# Demo.net
KiCad netlist of a schematic drawn in EAGLE
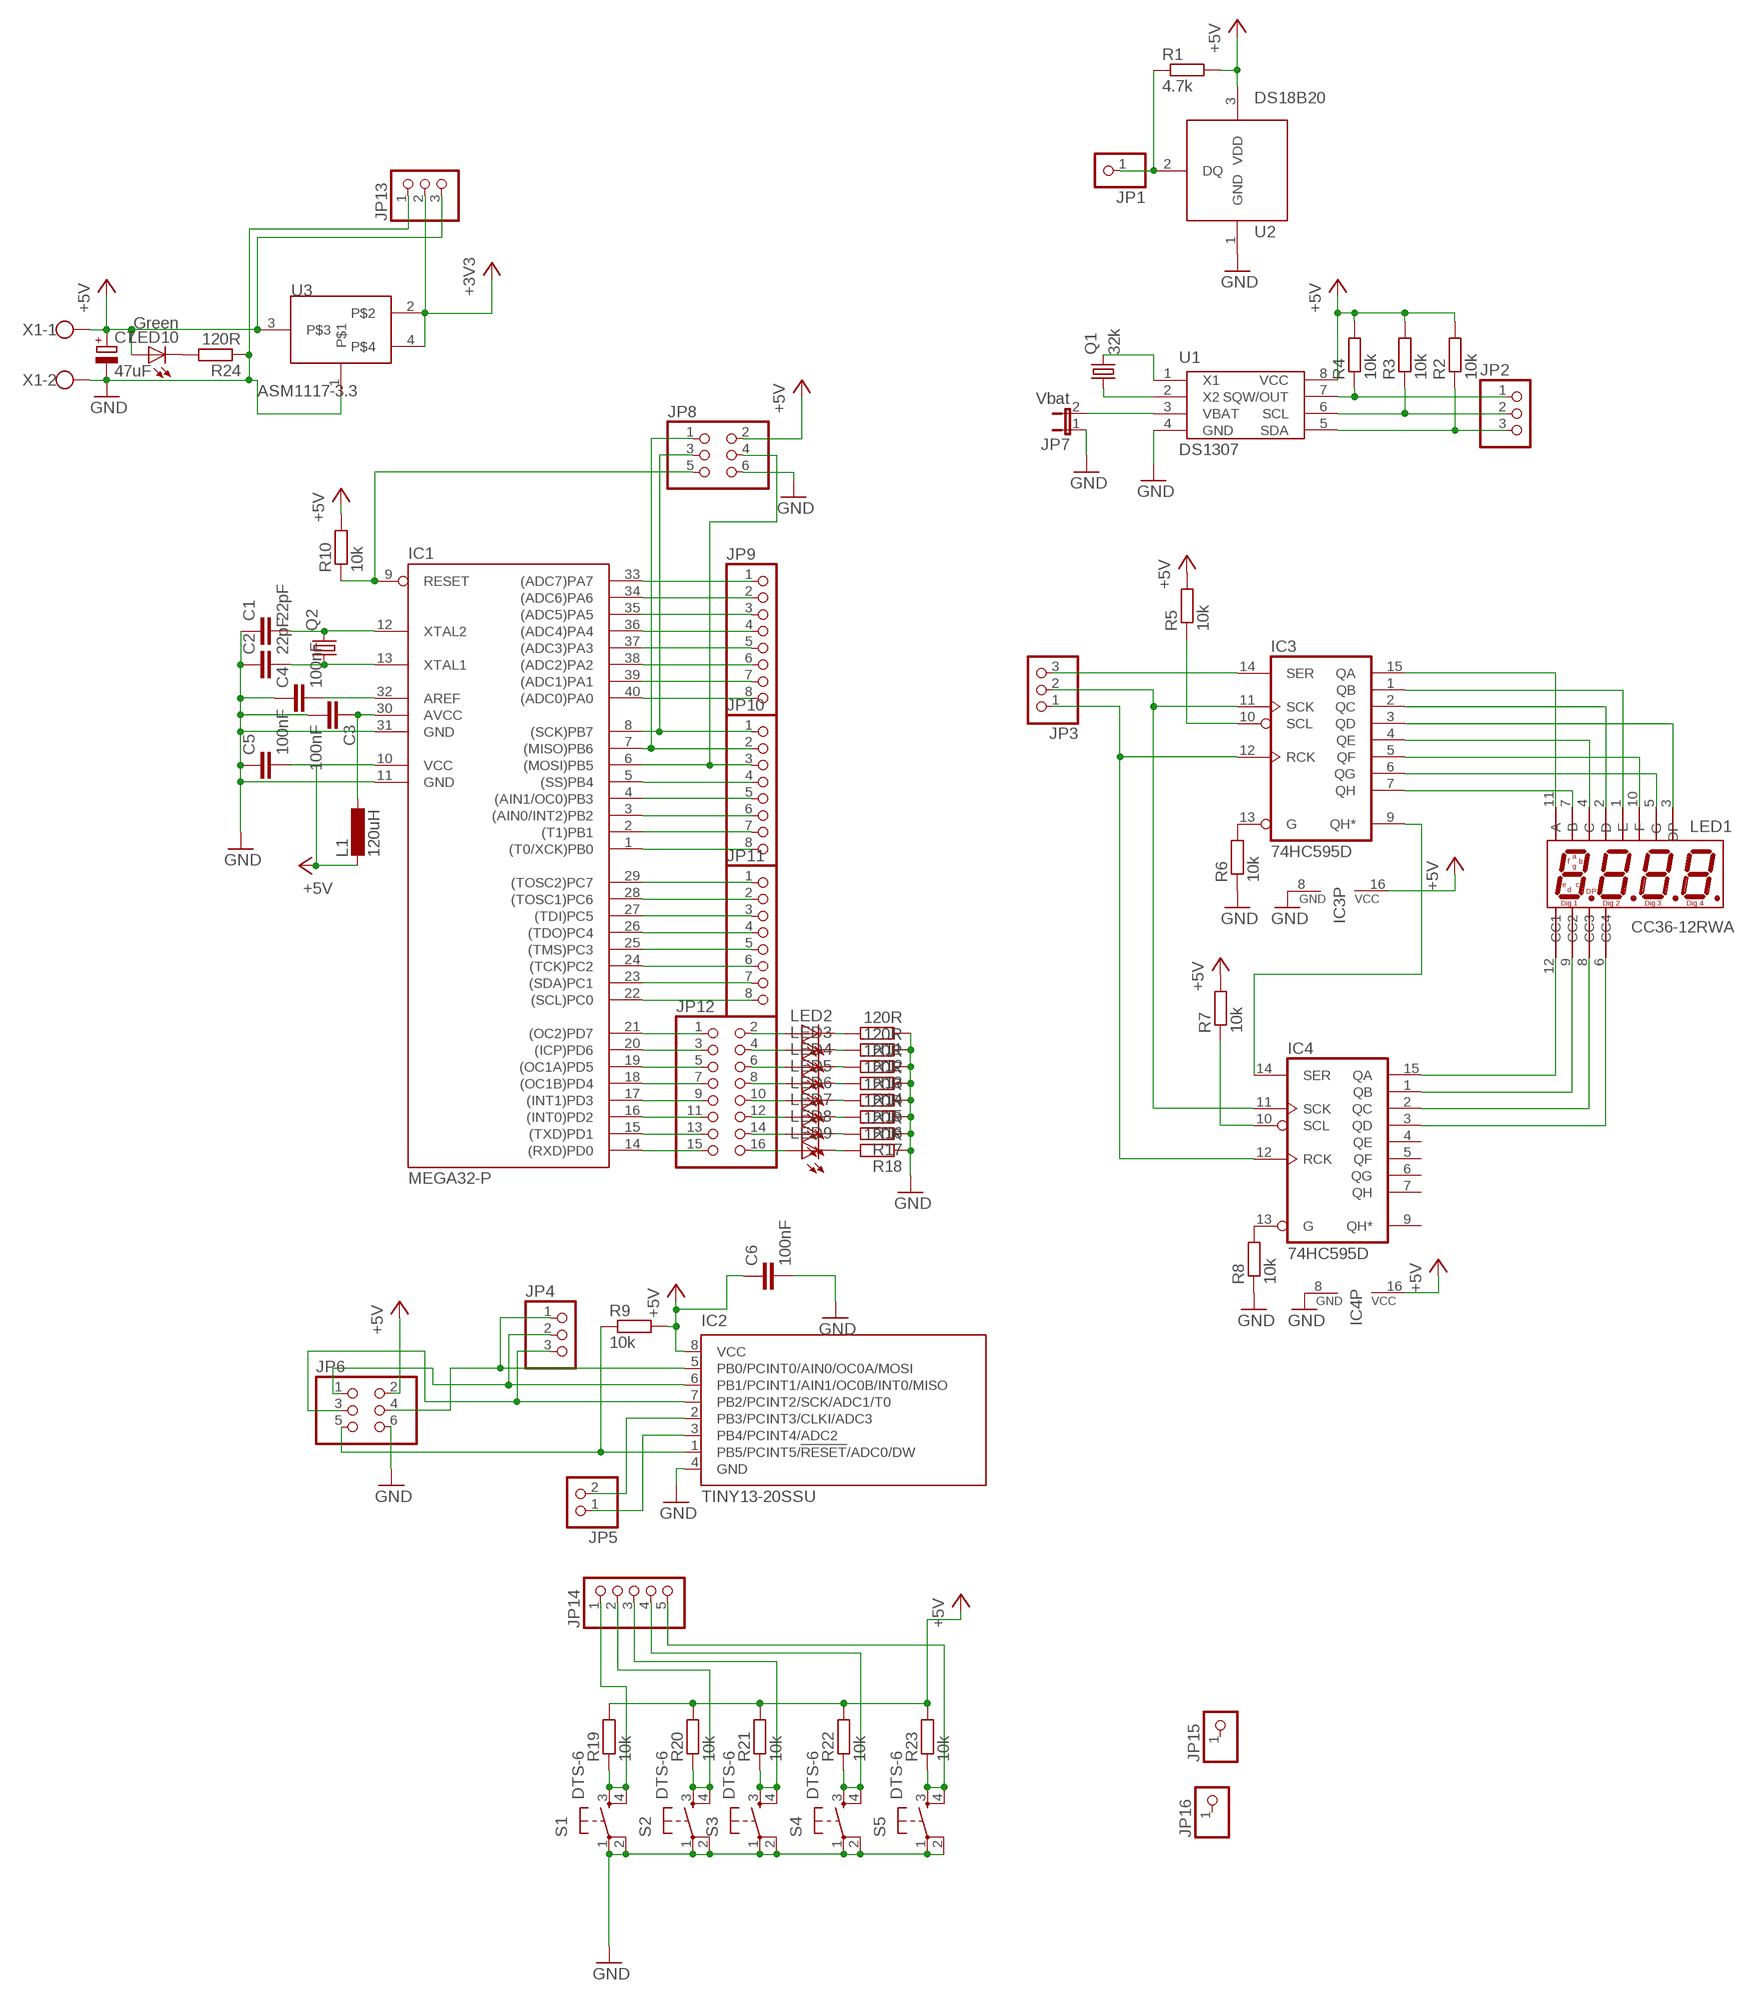
[diagram p0: schematic, sheet 1]

(export (version "E")
  (design (tool "Eeschema 10.0.6"))
  (components
    (comp (ref "C1")
      (value "22pF")
      (footprint "eagle-import:C0805")
      (libsource (lib "eagle-import") (part "C-EUC0805"))
    )
    (comp (ref "C2")
      (value "22pF")
      (footprint "eagle-import:C0805")
      (libsource (lib "eagle-import") (part "C-EUC0805"))
    )
    (comp (ref "C3")
      (value "100nF")
      (footprint "eagle-import:C0805")
      (libsource (lib "eagle-import") (part "C-EUC0805"))
    )
    (comp (ref "C4")
      (value "100nF")
      (footprint "eagle-import:C0805")
      (libsource (lib "eagle-import") (part "C-EUC0805"))
    )
    (comp (ref "C5")
      (value "100nF")
      (footprint "eagle-import:C0805")
      (libsource (lib "eagle-import") (part "C-EUC0805"))
    )
    (comp (ref "C6")
      (value "100nF")
      (footprint "eagle-import:C0805")
      (libsource (lib "eagle-import") (part "C-EUC0805"))
    )
    (comp (ref "C7")
      (value "47uF")
      (footprint "eagle-import:E2-5")
      (libsource (lib "eagle-import") (part "CPOL-EUE2-5"))
    )
    (comp (ref "IC1")
      (value "MEGA32-P")
      (footprint "eagle-import:DIL40")
      (fields (field (name "MPN") "ATMEGA32-16PU"))
      (libsource (lib "eagle-import") (part "MEGA32-P"))
    )
    (comp (ref "IC2")
      (value "TINY13-20SSU")
      (footprint "eagle-import:8S1")
      (fields (field (name "MPN") "ATTINY13-20SSU"))
      (libsource (lib "eagle-import") (part "TINY13SSU-20"))
    )
    (comp (ref "IC3")
      (value "74HC595D")
      (footprint "eagle-import:SO16")
      (libsource (lib "eagle-import") (part "74595DHC"))
    )
    (comp (ref "IC4")
      (value "74HC595D")
      (footprint "eagle-import:SO16")
      (libsource (lib "eagle-import") (part "74595DHC"))
    )
    (comp (ref "JP1")
      (value "PINHD-1X1")
      (footprint "eagle-import:1X01")
      (libsource (lib "eagle-import") (part "PINHD-1X1"))
    )
    (comp (ref "JP2")
      (value "PINHD-1X3")
      (footprint "eagle-import:1X03")
      (libsource (lib "eagle-import") (part "PINHD-1X3"))
    )
    (comp (ref "JP3")
      (value "PINHD-1X3")
      (footprint "eagle-import:1X03")
      (libsource (lib "eagle-import") (part "PINHD-1X3"))
    )
    (comp (ref "JP4")
      (value "PINHD-1X3")
      (footprint "eagle-import:1X03")
      (libsource (lib "eagle-import") (part "PINHD-1X3"))
    )
    (comp (ref "JP5")
      (value "PINHD-1X2")
      (footprint "eagle-import:1X02")
      (libsource (lib "eagle-import") (part "PINHD-1X2"))
    )
    (comp (ref "JP6")
      (value "PINHD-2X3")
      (footprint "eagle-import:2X03")
      (libsource (lib "eagle-import") (part "PINHD-2X3"))
    )
    (comp (ref "JP7")
      (value "Vbat")
      (footprint "eagle-import:JP1")
      (libsource (lib "eagle-import") (part "JP1E"))
    )
    (comp (ref "JP8")
      (value "PINHD-2X3")
      (footprint "eagle-import:2X03")
      (libsource (lib "eagle-import") (part "PINHD-2X3"))
    )
    (comp (ref "JP9")
      (value "PINHD-1X8")
      (footprint "eagle-import:1X08")
      (libsource (lib "eagle-import") (part "PINHD-1X8"))
    )
    (comp (ref "JP10")
      (value "PINHD-1X8")
      (footprint "eagle-import:1X08")
      (libsource (lib "eagle-import") (part "PINHD-1X8"))
    )
    (comp (ref "JP11")
      (value "PINHD-1X8")
      (footprint "eagle-import:1X08")
      (libsource (lib "eagle-import") (part "PINHD-1X8"))
    )
    (comp (ref "JP12")
      (value "PINHD-2X8")
      (footprint "eagle-import:2X08")
      (libsource (lib "eagle-import") (part "PINHD-2X8"))
    )
    (comp (ref "JP13")
      (value "PINHD-1X3")
      (footprint "eagle-import:1X03")
      (libsource (lib "eagle-import") (part "PINHD-1X3"))
    )
    (comp (ref "JP14")
      (value "PINHD-1X5")
      (footprint "eagle-import:1X05")
      (libsource (lib "eagle-import") (part "PINHD-1X5"))
    )
    (comp (ref "JP15")
      (value "PINHD-1X1")
      (footprint "eagle-import:1X01")
      (libsource (lib "eagle-import") (part "PINHD-1X1"))
    )
    (comp (ref "JP16")
      (value "PINHD-1X1")
      (footprint "eagle-import:1X01")
      (libsource (lib "eagle-import") (part "PINHD-1X1"))
    )
    (comp (ref "L1")
      (value "120uH")
      (footprint "eagle-import:0204V")
      (libsource (lib "eagle-import") (part "L-EU0204V"))
    )
    (comp (ref "LED1")
      (value "CC36-12RWA")
      (footprint "eagle-import:7SEG_4DIG")
      (libsource (lib "eagle-import") (part "CC36-12RWA"))
    )
    (comp (ref "LED2")
      (value "LEDSML0603")
      (footprint "eagle-import:SML0603")
      (libsource (lib "eagle-import") (part "LEDSML0603"))
    )
    (comp (ref "LED3")
      (value "LEDSML0603")
      (footprint "eagle-import:SML0603")
      (libsource (lib "eagle-import") (part "LEDSML0603"))
    )
    (comp (ref "LED4")
      (value "LEDSML0603")
      (footprint "eagle-import:SML0603")
      (libsource (lib "eagle-import") (part "LEDSML0603"))
    )
    (comp (ref "LED5")
      (value "LEDSML0603")
      (footprint "eagle-import:SML0603")
      (libsource (lib "eagle-import") (part "LEDSML0603"))
    )
    (comp (ref "LED6")
      (value "LEDSML0603")
      (footprint "eagle-import:SML0603")
      (libsource (lib "eagle-import") (part "LEDSML0603"))
    )
    (comp (ref "LED7")
      (value "LEDSML0603")
      (footprint "eagle-import:SML0603")
      (libsource (lib "eagle-import") (part "LEDSML0603"))
    )
    (comp (ref "LED8")
      (value "LEDSML0603")
      (footprint "eagle-import:SML0603")
      (libsource (lib "eagle-import") (part "LEDSML0603"))
    )
    (comp (ref "LED9")
      (value "LEDSML0603")
      (footprint "eagle-import:SML0603")
      (libsource (lib "eagle-import") (part "LEDSML0603"))
    )
    (comp (ref "LED10")
      (value "Green")
      (footprint "eagle-import:SML0603")
      (libsource (lib "eagle-import") (part "LEDSML0603"))
    )
    (comp (ref "Q1")
      (value "32k")
      (footprint "eagle-import:TC38H")
      (libsource (lib "eagle-import") (part "CRYSTALTC38H"))
    )
    (comp (ref "Q2")
      (value "CRYSTALHC49S")
      (footprint "eagle-import:HC49_S")
      (libsource (lib "eagle-import") (part "CRYSTALHC49S"))
    )
    (comp (ref "R1")
      (value "4.7k")
      (footprint "eagle-import:R0603")
      (libsource (lib "eagle-import") (part "R-EU_R0603"))
    )
    (comp (ref "R2")
      (value "10k")
      (footprint "eagle-import:R0603")
      (libsource (lib "eagle-import") (part "R-EU_R0603"))
    )
    (comp (ref "R3")
      (value "10k")
      (footprint "eagle-import:R0603")
      (libsource (lib "eagle-import") (part "R-EU_R0603"))
    )
    (comp (ref "R4")
      (value "10k")
      (footprint "eagle-import:R0603")
      (libsource (lib "eagle-import") (part "R-EU_R0603"))
    )
    (comp (ref "R5")
      (value "10k")
      (footprint "eagle-import:R0603")
      (libsource (lib "eagle-import") (part "R-EU_R0603"))
    )
    (comp (ref "R6")
      (value "10k")
      (footprint "eagle-import:R0603")
      (libsource (lib "eagle-import") (part "R-EU_R0603"))
    )
    (comp (ref "R7")
      (value "10k")
      (footprint "eagle-import:R0603")
      (libsource (lib "eagle-import") (part "R-EU_R0603"))
    )
    (comp (ref "R8")
      (value "10k")
      (footprint "eagle-import:R0603")
      (libsource (lib "eagle-import") (part "R-EU_R0603"))
    )
    (comp (ref "R9")
      (value "10k")
      (footprint "eagle-import:R0603")
      (libsource (lib "eagle-import") (part "R-EU_R0603"))
    )
    (comp (ref "R10")
      (value "10k")
      (footprint "eagle-import:R0603")
      (libsource (lib "eagle-import") (part "R-EU_R0603"))
    )
    (comp (ref "R11")
      (value "120R")
      (footprint "eagle-import:R0603")
      (libsource (lib "eagle-import") (part "R-EU_R0603"))
    )
    (comp (ref "R12")
      (value "120R")
      (footprint "eagle-import:R0603")
      (libsource (lib "eagle-import") (part "R-EU_R0603"))
    )
    (comp (ref "R13")
      (value "120R")
      (footprint "eagle-import:R0603")
      (libsource (lib "eagle-import") (part "R-EU_R0603"))
    )
    (comp (ref "R14")
      (value "120R")
      (footprint "eagle-import:R0603")
      (libsource (lib "eagle-import") (part "R-EU_R0603"))
    )
    (comp (ref "R15")
      (value "120R")
      (footprint "eagle-import:R0603")
      (libsource (lib "eagle-import") (part "R-EU_R0603"))
    )
    (comp (ref "R16")
      (value "120R")
      (footprint "eagle-import:R0603")
      (libsource (lib "eagle-import") (part "R-EU_R0603"))
    )
    (comp (ref "R17")
      (value "120R")
      (footprint "eagle-import:R0603")
      (libsource (lib "eagle-import") (part "R-EU_R0603"))
    )
    (comp (ref "R18")
      (value "120R")
      (footprint "eagle-import:R0603")
      (libsource (lib "eagle-import") (part "R-EU_R0603"))
    )
    (comp (ref "R19")
      (value "10k")
      (footprint "eagle-import:R0603")
      (libsource (lib "eagle-import") (part "R-EU_R0603"))
    )
    (comp (ref "R20")
      (value "10k")
      (footprint "eagle-import:R0603")
      (libsource (lib "eagle-import") (part "R-EU_R0603"))
    )
    (comp (ref "R21")
      (value "10k")
      (footprint "eagle-import:R0603")
      (libsource (lib "eagle-import") (part "R-EU_R0603"))
    )
    (comp (ref "R22")
      (value "10k")
      (footprint "eagle-import:R0603")
      (libsource (lib "eagle-import") (part "R-EU_R0603"))
    )
    (comp (ref "R23")
      (value "10k")
      (footprint "eagle-import:R0603")
      (libsource (lib "eagle-import") (part "R-EU_R0603"))
    )
    (comp (ref "R24")
      (value "120R")
      (footprint "eagle-import:R0603")
      (libsource (lib "eagle-import") (part "R-EU_R0603"))
    )
    (comp (ref "S1")
      (value "DTS-6")
      (footprint "eagle-import:DTS-6")
      (libsource (lib "eagle-import") (part "DTS-6"))
    )
    (comp (ref "S2")
      (value "DTS-6")
      (footprint "eagle-import:DTS-6")
      (libsource (lib "eagle-import") (part "DTS-6"))
    )
    (comp (ref "S3")
      (value "DTS-6")
      (footprint "eagle-import:DTS-6")
      (libsource (lib "eagle-import") (part "DTS-6"))
    )
    (comp (ref "S4")
      (value "DTS-6")
      (footprint "eagle-import:DTS-6")
      (libsource (lib "eagle-import") (part "DTS-6"))
    )
    (comp (ref "S5")
      (value "DTS-6")
      (footprint "eagle-import:DTS-6")
      (libsource (lib "eagle-import") (part "DTS-6"))
    )
    (comp (ref "U1")
      (value "DS1307")
      (footprint "eagle-import:SOP08")
      (libsource (lib "eagle-import") (part "DS1307"))
    )
    (comp (ref "U2")
      (value "DS18B20")
      (footprint "eagle-import:TO92")
      (libsource (lib "eagle-import") (part "DS18B20"))
    )
    (comp (ref "U3")
      (value "ASM1117-3.3")
      (footprint "eagle-import:SOT223")
      (libsource (lib "eagle-import") (part "ASM1117-3.3"))
    )
    (comp (ref "X1")
      (value "W237-102")
      (footprint "eagle-import:W237-102")
      (fields (field (name "MPN") "237-102"))
      (libsource (lib "eagle-import") (part "W237-102"))
    )
  )
  (nets
    (net (code "1") (name "+3V3") (class "Default")
      (node (ref "JP13") (pin "2") (pinfunction "2_2") (pintype "passive"))
      (node (ref "U3") (pin "2") (pinfunction "P$2_2") (pintype "bidirectional"))
      (node (ref "U3") (pin "4") (pinfunction "P$4_4") (pintype "bidirectional"))
    )
    (net (code "2") (name "+5V") (class "Default")
      (node (ref "C5") (pin "2") (pinfunction "2_2") (pintype "passive"))
      (node (ref "C6") (pin "1") (pinfunction "1_1") (pintype "passive"))
      (node (ref "C7") (pin "+") (pinfunction "+_+") (pintype "passive"))
      (node (ref "IC1") (pin "10") (pinfunction "VCC_10") (pintype "power_in"))
      (node (ref "IC2") (pin "8") (pinfunction "VCC_8") (pintype "power_in"))
      (node (ref "IC3") (pin "16") (pinfunction "VCC_16") (pintype "power_in"))
      (node (ref "IC4") (pin "16") (pinfunction "VCC_16") (pintype "power_in"))
      (node (ref "JP13") (pin "3") (pinfunction "3_3") (pintype "passive"))
      (node (ref "JP6") (pin "2") (pinfunction "2_2") (pintype "passive"))
      (node (ref "JP8") (pin "2") (pinfunction "2_2") (pintype "passive"))
      (node (ref "L1") (pin "2") (pinfunction "2_2") (pintype "passive"))
      (node (ref "LED10") (pin "A") (pinfunction "A_A") (pintype "passive"))
      (node (ref "R1") (pin "2") (pinfunction "2_2") (pintype "passive"))
      (node (ref "R10") (pin "2") (pinfunction "2_2") (pintype "passive"))
      (node (ref "R19") (pin "2") (pinfunction "2_2") (pintype "passive"))
      (node (ref "R2") (pin "2") (pinfunction "2_2") (pintype "passive"))
      (node (ref "R20") (pin "2") (pinfunction "2_2") (pintype "passive"))
      (node (ref "R21") (pin "2") (pinfunction "2_2") (pintype "passive"))
      (node (ref "R22") (pin "2") (pinfunction "2_2") (pintype "passive"))
      (node (ref "R23") (pin "2") (pinfunction "2_2") (pintype "passive"))
      (node (ref "R3") (pin "2") (pinfunction "2_2") (pintype "passive"))
      (node (ref "R4") (pin "2") (pinfunction "2_2") (pintype "passive"))
      (node (ref "R5") (pin "2") (pinfunction "2_2") (pintype "passive"))
      (node (ref "R7") (pin "2") (pinfunction "2_2") (pintype "passive"))
      (node (ref "R9") (pin "2") (pinfunction "2_2") (pintype "passive"))
      (node (ref "U1") (pin "8") (pinfunction "VCC_8") (pintype "power_in"))
      (node (ref "U2") (pin "3") (pinfunction "VDD_3") (pintype "power_in"))
      (node (ref "U3") (pin "3") (pinfunction "P$3_3") (pintype "bidirectional"))
      (node (ref "X1") (pin "1") (pinfunction "KL_1") (pintype "passive"))
    )
    (net (code "3") (name "GND") (class "Default")
      (node (ref "C1") (pin "1") (pinfunction "1_1") (pintype "passive"))
      (node (ref "C2") (pin "1") (pinfunction "1_1") (pintype "passive"))
      (node (ref "C3") (pin "2") (pinfunction "2_2") (pintype "passive"))
      (node (ref "C4") (pin "1") (pinfunction "1_1") (pintype "passive"))
      (node (ref "C5") (pin "1") (pinfunction "1_1") (pintype "passive"))
      (node (ref "C6") (pin "2") (pinfunction "2_2") (pintype "passive"))
      (node (ref "C7") (pin "-") (pinfunction "-_-") (pintype "passive"))
      (node (ref "IC1") (pin "11") (pinfunction "GND_11") (pintype "power_in"))
      (node (ref "IC1") (pin "31") (pinfunction "GND_31") (pintype "power_in"))
      (node (ref "IC2") (pin "4") (pinfunction "GND_4") (pintype "power_in"))
      (node (ref "IC3") (pin "8") (pinfunction "GND_8") (pintype "power_in"))
      (node (ref "IC4") (pin "8") (pinfunction "GND_8") (pintype "power_in"))
      (node (ref "JP13") (pin "1") (pinfunction "1_1") (pintype "passive"))
      (node (ref "JP6") (pin "6") (pinfunction "6_6") (pintype "passive"))
      (node (ref "JP7") (pin "1") (pinfunction "1_1") (pintype "passive"))
      (node (ref "JP8") (pin "6") (pinfunction "6_6") (pintype "passive"))
      (node (ref "R11") (pin "1") (pinfunction "1_1") (pintype "passive"))
      (node (ref "R12") (pin "1") (pinfunction "1_1") (pintype "passive"))
      (node (ref "R13") (pin "1") (pinfunction "1_1") (pintype "passive"))
      (node (ref "R14") (pin "1") (pinfunction "1_1") (pintype "passive"))
      (node (ref "R15") (pin "1") (pinfunction "1_1") (pintype "passive"))
      (node (ref "R16") (pin "1") (pinfunction "1_1") (pintype "passive"))
      (node (ref "R17") (pin "1") (pinfunction "1_1") (pintype "passive"))
      (node (ref "R18") (pin "1") (pinfunction "1_1") (pintype "passive"))
      (node (ref "R24") (pin "1") (pinfunction "1_1") (pintype "passive"))
      (node (ref "R6") (pin "1") (pinfunction "1_1") (pintype "passive"))
      (node (ref "R8") (pin "1") (pinfunction "1_1") (pintype "passive"))
      (node (ref "S1") (pin "1") (pinfunction "1_1") (pintype "passive"))
      (node (ref "S1") (pin "2") (pinfunction "2_2") (pintype "passive"))
      (node (ref "S2") (pin "1") (pinfunction "1_1") (pintype "passive"))
      (node (ref "S2") (pin "2") (pinfunction "2_2") (pintype "passive"))
      (node (ref "S3") (pin "1") (pinfunction "1_1") (pintype "passive"))
      (node (ref "S3") (pin "2") (pinfunction "2_2") (pintype "passive"))
      (node (ref "S4") (pin "1") (pinfunction "1_1") (pintype "passive"))
      (node (ref "S4") (pin "2") (pinfunction "2_2") (pintype "passive"))
      (node (ref "S5") (pin "1") (pinfunction "1_1") (pintype "passive"))
      (node (ref "S5") (pin "2") (pinfunction "2_2") (pintype "passive"))
      (node (ref "U1") (pin "4") (pinfunction "GND_4") (pintype "power_in"))
      (node (ref "U2") (pin "1") (pinfunction "GND_1") (pintype "power_in"))
      (node (ref "U3") (pin "1") (pinfunction "P$1_1") (pintype "bidirectional"))
      (node (ref "X1") (pin "2") (pinfunction "KL_2") (pintype "passive"))
    )
    (net (code "4") (name "Net-(IC1-(ADC0)PA0)") (class "Default")
      (node (ref "IC1") (pin "40") (pinfunction "(ADC0)PA0_40") (pintype "bidirectional"))
      (node (ref "JP9") (pin "8") (pinfunction "8_8") (pintype "passive"))
    )
    (net (code "5") (name "Net-(IC1-(ADC1)PA1)") (class "Default")
      (node (ref "IC1") (pin "39") (pinfunction "(ADC1)PA1_39") (pintype "bidirectional"))
      (node (ref "JP9") (pin "7") (pinfunction "7_7") (pintype "passive"))
    )
    (net (code "6") (name "Net-(IC1-(ADC2)PA2)") (class "Default")
      (node (ref "IC1") (pin "38") (pinfunction "(ADC2)PA2_38") (pintype "bidirectional"))
      (node (ref "JP9") (pin "6") (pinfunction "6_6") (pintype "passive"))
    )
    (net (code "7") (name "Net-(IC1-(ADC3)PA3)") (class "Default")
      (node (ref "IC1") (pin "37") (pinfunction "(ADC3)PA3_37") (pintype "bidirectional"))
      (node (ref "JP9") (pin "5") (pinfunction "5_5") (pintype "passive"))
    )
    (net (code "8") (name "Net-(IC1-(ADC4)PA4)") (class "Default")
      (node (ref "IC1") (pin "36") (pinfunction "(ADC4)PA4_36") (pintype "bidirectional"))
      (node (ref "JP9") (pin "4") (pinfunction "4_4") (pintype "passive"))
    )
    (net (code "9") (name "Net-(IC1-(ADC5)PA5)") (class "Default")
      (node (ref "IC1") (pin "35") (pinfunction "(ADC5)PA5_35") (pintype "bidirectional"))
      (node (ref "JP9") (pin "3") (pinfunction "3_3") (pintype "passive"))
    )
    (net (code "10") (name "Net-(IC1-(ADC6)PA6)") (class "Default")
      (node (ref "IC1") (pin "34") (pinfunction "(ADC6)PA6_34") (pintype "bidirectional"))
      (node (ref "JP9") (pin "2") (pinfunction "2_2") (pintype "passive"))
    )
    (net (code "11") (name "Net-(IC1-(ADC7)PA7)") (class "Default")
      (node (ref "IC1") (pin "33") (pinfunction "(ADC7)PA7_33") (pintype "bidirectional"))
      (node (ref "JP9") (pin "1") (pinfunction "1_1") (pintype "passive"))
    )
    (net (code "12") (name "Net-(IC1-(AIN0{slash}INT2)PB2)") (class "Default")
      (node (ref "IC1") (pin "3") (pinfunction "(AIN0/INT2)PB2_3") (pintype "bidirectional"))
      (node (ref "JP10") (pin "6") (pinfunction "6_6") (pintype "passive"))
    )
    (net (code "13") (name "Net-(IC1-(AIN1{slash}OC0)PB3)") (class "Default")
      (node (ref "IC1") (pin "4") (pinfunction "(AIN1/OC0)PB3_4") (pintype "bidirectional"))
      (node (ref "JP10") (pin "5") (pinfunction "5_5") (pintype "passive"))
    )
    (net (code "14") (name "Net-(IC1-(ICP)PD6)") (class "Default")
      (node (ref "IC1") (pin "20") (pinfunction "(ICP)PD6_20") (pintype "bidirectional"))
      (node (ref "JP12") (pin "3") (pinfunction "3_3") (pintype "passive"))
    )
    (net (code "15") (name "Net-(IC1-(INT0)PD2)") (class "Default")
      (node (ref "IC1") (pin "16") (pinfunction "(INT0)PD2_16") (pintype "bidirectional"))
      (node (ref "JP12") (pin "11") (pinfunction "11_11") (pintype "passive"))
    )
    (net (code "16") (name "Net-(IC1-(INT1)PD3)") (class "Default")
      (node (ref "IC1") (pin "17") (pinfunction "(INT1)PD3_17") (pintype "bidirectional"))
      (node (ref "JP12") (pin "9") (pinfunction "9_9") (pintype "passive"))
    )
    (net (code "17") (name "Net-(IC1-(MISO)PB6)") (class "Default")
      (node (ref "IC1") (pin "7") (pinfunction "(MISO)PB6_7") (pintype "bidirectional"))
      (node (ref "JP10") (pin "2") (pinfunction "2_2") (pintype "passive"))
      (node (ref "JP8") (pin "1") (pinfunction "1_1") (pintype "passive"))
    )
    (net (code "18") (name "Net-(IC1-(MOSI)PB5)") (class "Default")
      (node (ref "IC1") (pin "6") (pinfunction "(MOSI)PB5_6") (pintype "bidirectional"))
      (node (ref "JP10") (pin "3") (pinfunction "3_3") (pintype "passive"))
      (node (ref "JP8") (pin "4") (pinfunction "4_4") (pintype "passive"))
    )
    (net (code "19") (name "Net-(IC1-(OC1A)PD5)") (class "Default")
      (node (ref "IC1") (pin "19") (pinfunction "(OC1A)PD5_19") (pintype "bidirectional"))
      (node (ref "JP12") (pin "5") (pinfunction "5_5") (pintype "passive"))
    )
    (net (code "20") (name "Net-(IC1-(OC1B)PD4)") (class "Default")
      (node (ref "IC1") (pin "18") (pinfunction "(OC1B)PD4_18") (pintype "bidirectional"))
      (node (ref "JP12") (pin "7") (pinfunction "7_7") (pintype "passive"))
    )
    (net (code "21") (name "Net-(IC1-(OC2)PD7)") (class "Default")
      (node (ref "IC1") (pin "21") (pinfunction "(OC2)PD7_21") (pintype "bidirectional"))
      (node (ref "JP12") (pin "1") (pinfunction "1_1") (pintype "passive"))
    )
    (net (code "22") (name "Net-(IC1-(RXD)PD0)") (class "Default")
      (node (ref "IC1") (pin "14") (pinfunction "(RXD)PD0_14") (pintype "bidirectional"))
      (node (ref "JP12") (pin "15") (pinfunction "15_15") (pintype "passive"))
    )
    (net (code "23") (name "Net-(IC1-(SCK)PB7)") (class "Default")
      (node (ref "IC1") (pin "8") (pinfunction "(SCK)PB7_8") (pintype "bidirectional"))
      (node (ref "JP10") (pin "1") (pinfunction "1_1") (pintype "passive"))
      (node (ref "JP8") (pin "3") (pinfunction "3_3") (pintype "passive"))
    )
    (net (code "24") (name "Net-(IC1-(SCL)PC0)") (class "Default")
      (node (ref "IC1") (pin "22") (pinfunction "(SCL)PC0_22") (pintype "bidirectional"))
      (node (ref "JP11") (pin "8") (pinfunction "8_8") (pintype "passive"))
    )
    (net (code "25") (name "Net-(IC1-(SDA)PC1)") (class "Default")
      (node (ref "IC1") (pin "23") (pinfunction "(SDA)PC1_23") (pintype "bidirectional"))
      (node (ref "JP11") (pin "7") (pinfunction "7_7") (pintype "passive"))
    )
    (net (code "26") (name "Net-(IC1-(SS)PB4)") (class "Default")
      (node (ref "IC1") (pin "5") (pinfunction "(SS)PB4_5") (pintype "bidirectional"))
      (node (ref "JP10") (pin "4") (pinfunction "4_4") (pintype "passive"))
    )
    (net (code "27") (name "Net-(IC1-(T0{slash}XCK)PB0)") (class "Default")
      (node (ref "IC1") (pin "1") (pinfunction "(T0/XCK)PB0_1") (pintype "bidirectional"))
      (node (ref "JP10") (pin "8") (pinfunction "8_8") (pintype "passive"))
    )
    (net (code "28") (name "Net-(IC1-(T1)PB1)") (class "Default")
      (node (ref "IC1") (pin "2") (pinfunction "(T1)PB1_2") (pintype "bidirectional"))
      (node (ref "JP10") (pin "7") (pinfunction "7_7") (pintype "passive"))
    )
    (net (code "29") (name "Net-(IC1-(TCK)PC2)") (class "Default")
      (node (ref "IC1") (pin "24") (pinfunction "(TCK)PC2_24") (pintype "bidirectional"))
      (node (ref "JP11") (pin "6") (pinfunction "6_6") (pintype "passive"))
    )
    (net (code "30") (name "Net-(IC1-(TDI)PC5)") (class "Default")
      (node (ref "IC1") (pin "27") (pinfunction "(TDI)PC5_27") (pintype "bidirectional"))
      (node (ref "JP11") (pin "3") (pinfunction "3_3") (pintype "passive"))
    )
    (net (code "31") (name "Net-(IC1-(TDO)PC4)") (class "Default")
      (node (ref "IC1") (pin "26") (pinfunction "(TDO)PC4_26") (pintype "bidirectional"))
      (node (ref "JP11") (pin "4") (pinfunction "4_4") (pintype "passive"))
    )
    (net (code "32") (name "Net-(IC1-(TMS)PC3)") (class "Default")
      (node (ref "IC1") (pin "25") (pinfunction "(TMS)PC3_25") (pintype "bidirectional"))
      (node (ref "JP11") (pin "5") (pinfunction "5_5") (pintype "passive"))
    )
    (net (code "33") (name "Net-(IC1-(TOSC1)PC6)") (class "Default")
      (node (ref "IC1") (pin "28") (pinfunction "(TOSC1)PC6_28") (pintype "bidirectional"))
      (node (ref "JP11") (pin "2") (pinfunction "2_2") (pintype "passive"))
    )
    (net (code "34") (name "Net-(IC1-(TOSC2)PC7)") (class "Default")
      (node (ref "IC1") (pin "29") (pinfunction "(TOSC2)PC7_29") (pintype "bidirectional"))
      (node (ref "JP11") (pin "1") (pinfunction "1_1") (pintype "passive"))
    )
    (net (code "35") (name "Net-(IC1-(TXD)PD1)") (class "Default")
      (node (ref "IC1") (pin "15") (pinfunction "(TXD)PD1_15") (pintype "bidirectional"))
      (node (ref "JP12") (pin "13") (pinfunction "13_13") (pintype "passive"))
    )
    (net (code "36") (name "Net-(IC1-AREF)") (class "Default")
      (node (ref "C4") (pin "2") (pinfunction "2_2") (pintype "passive"))
      (node (ref "IC1") (pin "32") (pinfunction "AREF_32") (pintype "passive"))
    )
    (net (code "37") (name "Net-(IC1-AVCC)") (class "Default")
      (node (ref "C3") (pin "1") (pinfunction "1_1") (pintype "passive"))
      (node (ref "IC1") (pin "30") (pinfunction "AVCC_30") (pintype "power_in"))
      (node (ref "L1") (pin "1") (pinfunction "1_1") (pintype "passive"))
    )
    (net (code "38") (name "Net-(IC1-RESET)") (class "Default")
      (node (ref "IC1") (pin "9") (pinfunction "RESET_9") (pintype "input"))
      (node (ref "JP8") (pin "5") (pinfunction "5_5") (pintype "passive"))
      (node (ref "R10") (pin "1") (pinfunction "1_1") (pintype "passive"))
    )
    (net (code "39") (name "Net-(IC1-XTAL1)") (class "Default")
      (node (ref "C2") (pin "2") (pinfunction "2_2") (pintype "passive"))
      (node (ref "IC1") (pin "13") (pinfunction "XTAL1_13") (pintype "bidirectional"))
      (node (ref "Q2") (pin "1") (pinfunction "1_1") (pintype "passive"))
    )
    (net (code "40") (name "Net-(IC1-XTAL2)") (class "Default")
      (node (ref "C1") (pin "2") (pinfunction "2_2") (pintype "passive"))
      (node (ref "IC1") (pin "12") (pinfunction "XTAL2_12") (pintype "bidirectional"))
      (node (ref "Q2") (pin "2") (pinfunction "2_2") (pintype "passive"))
    )
    (net (code "41") (name "Net-(IC2-PB0{slash}PCINT0{slash}AIN0{slash}OC0A{slash}MOSI)") (class "Default")
      (node (ref "IC2") (pin "5") (pinfunction "PB0/PCINT0/AIN0/OC0A/MOSI_5") (pintype "bidirectional"))
      (node (ref "JP4") (pin "1") (pinfunction "1_1") (pintype "passive"))
      (node (ref "JP6") (pin "4") (pinfunction "4_4") (pintype "passive"))
    )
    (net (code "42") (name "Net-(IC2-PB1{slash}PCINT1{slash}AIN1{slash}OC0B{slash}INT0{slash}MISO)") (class "Default")
      (node (ref "IC2") (pin "6") (pinfunction "PB1/PCINT1/AIN1/OC0B/INT0/MISO_6") (pintype "bidirectional"))
      (node (ref "JP4") (pin "2") (pinfunction "2_2") (pintype "passive"))
      (node (ref "JP6") (pin "1") (pinfunction "1_1") (pintype "passive"))
    )
    (net (code "43") (name "Net-(IC2-PB2{slash}PCINT2{slash}SCK{slash}ADC1{slash}T0)") (class "Default")
      (node (ref "IC2") (pin "7") (pinfunction "PB2/PCINT2/SCK/ADC1/T0_7") (pintype "bidirectional"))
      (node (ref "JP4") (pin "3") (pinfunction "3_3") (pintype "passive"))
      (node (ref "JP6") (pin "3") (pinfunction "3_3") (pintype "passive"))
    )
    (net (code "44") (name "Net-(IC2-PB3{slash}PCINT3{slash}CLKI{slash}ADC3)") (class "Default")
      (node (ref "IC2") (pin "2") (pinfunction "PB3/PCINT3/CLKI/ADC3_2") (pintype "bidirectional"))
      (node (ref "JP5") (pin "2") (pinfunction "2_2") (pintype "passive"))
    )
    (net (code "45") (name "Net-(IC2-PB4{slash}PCINT4{slash}ADC2)") (class "Default")
      (node (ref "IC2") (pin "3") (pinfunction "PB4/PCINT4/ADC2_3") (pintype "bidirectional"))
      (node (ref "JP5") (pin "1") (pinfunction "1_1") (pintype "passive"))
    )
    (net (code "46") (name "Net-(IC2-PB5{slash}PCINT5{slash}~{RESET}{slash}ADC0{slash}DW)") (class "Default")
      (node (ref "IC2") (pin "1") (pinfunction "PB5/PCINT5/~{RESET}/ADC0/DW_1") (pintype "bidirectional"))
      (node (ref "JP6") (pin "5") (pinfunction "5_5") (pintype "passive"))
      (node (ref "R9") (pin "1") (pinfunction "1_1") (pintype "passive"))
    )
    (net (code "47") (name "Net-(IC3A-G)") (class "Default")
      (node (ref "IC3") (pin "13") (pinfunction "G_13") (pintype "input"))
      (node (ref "R6") (pin "2") (pinfunction "2_2") (pintype "passive"))
    )
    (net (code "48") (name "Net-(IC3A-QA)") (class "Default")
      (node (ref "IC3") (pin "15") (pinfunction "QA_15") (pintype "tri_state"))
      (node (ref "LED1") (pin "11") (pinfunction "A_11") (pintype "input"))
    )
    (net (code "49") (name "Net-(IC3A-QB)") (class "Default")
      (node (ref "IC3") (pin "1") (pinfunction "QB_1") (pintype "tri_state"))
      (node (ref "LED1") (pin "1") (pinfunction "E_1") (pintype "input"))
    )
    (net (code "50") (name "Net-(IC3A-QC)") (class "Default")
      (node (ref "IC3") (pin "2") (pinfunction "QC_2") (pintype "tri_state"))
      (node (ref "LED1") (pin "2") (pinfunction "D_2") (pintype "input"))
    )
    (net (code "51") (name "Net-(IC3A-QD)") (class "Default")
      (node (ref "IC3") (pin "3") (pinfunction "QD_3") (pintype "tri_state"))
      (node (ref "LED1") (pin "3") (pinfunction "DP_3") (pintype "input"))
    )
    (net (code "52") (name "Net-(IC3A-QE)") (class "Default")
      (node (ref "IC3") (pin "4") (pinfunction "QE_4") (pintype "tri_state"))
      (node (ref "LED1") (pin "4") (pinfunction "C_4") (pintype "input"))
    )
    (net (code "53") (name "Net-(IC3A-QF)") (class "Default")
      (node (ref "IC3") (pin "5") (pinfunction "QF_5") (pintype "tri_state"))
      (node (ref "LED1") (pin "10") (pinfunction "F_10") (pintype "input"))
    )
    (net (code "54") (name "Net-(IC3A-QG)") (class "Default")
      (node (ref "IC3") (pin "6") (pinfunction "QG_6") (pintype "tri_state"))
      (node (ref "LED1") (pin "5") (pinfunction "G_5") (pintype "input"))
    )
    (net (code "55") (name "Net-(IC3A-QH)") (class "Default")
      (node (ref "IC3") (pin "7") (pinfunction "QH_7") (pintype "tri_state"))
      (node (ref "LED1") (pin "7") (pinfunction "B_7") (pintype "input"))
    )
    (net (code "56") (name "Net-(IC3A-QH*)") (class "Default")
      (node (ref "IC3") (pin "9") (pinfunction "QH*_9") (pintype "tri_state"))
      (node (ref "IC4") (pin "14") (pinfunction "SER_14") (pintype "input"))
    )
    (net (code "57") (name "Net-(IC3A-RCK)") (class "Default")
      (node (ref "IC3") (pin "12") (pinfunction "RCK_12") (pintype "input"))
      (node (ref "IC4") (pin "12") (pinfunction "RCK_12") (pintype "input"))
      (node (ref "JP3") (pin "1") (pinfunction "1_1") (pintype "passive"))
    )
    (net (code "58") (name "Net-(IC3A-SCK)") (class "Default")
      (node (ref "IC3") (pin "11") (pinfunction "SCK_11") (pintype "input"))
      (node (ref "IC4") (pin "11") (pinfunction "SCK_11") (pintype "input"))
      (node (ref "JP3") (pin "2") (pinfunction "2_2") (pintype "passive"))
    )
    (net (code "59") (name "Net-(IC3A-SCL)") (class "Default")
      (node (ref "IC3") (pin "10") (pinfunction "SCL_10") (pintype "input"))
      (node (ref "R5") (pin "1") (pinfunction "1_1") (pintype "passive"))
    )
    (net (code "60") (name "Net-(IC3A-SER)") (class "Default")
      (node (ref "IC3") (pin "14") (pinfunction "SER_14") (pintype "input"))
      (node (ref "JP3") (pin "3") (pinfunction "3_3") (pintype "passive"))
    )
    (net (code "61") (name "Net-(IC4A-G)") (class "Default")
      (node (ref "IC4") (pin "13") (pinfunction "G_13") (pintype "input"))
      (node (ref "R8") (pin "2") (pinfunction "2_2") (pintype "passive"))
    )
    (net (code "62") (name "Net-(IC4A-QA)") (class "Default")
      (node (ref "IC4") (pin "15") (pinfunction "QA_15") (pintype "tri_state"))
      (node (ref "LED1") (pin "12") (pinfunction "CC1_12") (pintype "input"))
    )
    (net (code "63") (name "Net-(IC4A-QB)") (class "Default")
      (node (ref "IC4") (pin "1") (pinfunction "QB_1") (pintype "tri_state"))
      (node (ref "LED1") (pin "9") (pinfunction "CC2_9") (pintype "input"))
    )
    (net (code "64") (name "Net-(IC4A-QC)") (class "Default")
      (node (ref "IC4") (pin "2") (pinfunction "QC_2") (pintype "tri_state"))
      (node (ref "LED1") (pin "8") (pinfunction "CC3_8") (pintype "input"))
    )
    (net (code "65") (name "Net-(IC4A-QD)") (class "Default")
      (node (ref "IC4") (pin "3") (pinfunction "QD_3") (pintype "tri_state"))
      (node (ref "LED1") (pin "6") (pinfunction "CC4_6") (pintype "input"))
    )
    (net (code "66") (name "Net-(IC4A-SCL)") (class "Default")
      (node (ref "IC4") (pin "10") (pinfunction "SCL_10") (pintype "input"))
      (node (ref "R7") (pin "1") (pinfunction "1_1") (pintype "passive"))
    )
    (net (code "67") (name "Net-(JP12-Pad2)") (class "Default")
      (node (ref "JP12") (pin "2") (pinfunction "2_2") (pintype "passive"))
      (node (ref "LED2") (pin "A") (pinfunction "A_A") (pintype "passive"))
    )
    (net (code "68") (name "Net-(JP12-Pad4)") (class "Default")
      (node (ref "JP12") (pin "4") (pinfunction "4_4") (pintype "passive"))
      (node (ref "LED3") (pin "A") (pinfunction "A_A") (pintype "passive"))
    )
    (net (code "69") (name "Net-(JP12-Pad6)") (class "Default")
      (node (ref "JP12") (pin "6") (pinfunction "6_6") (pintype "passive"))
      (node (ref "LED4") (pin "A") (pinfunction "A_A") (pintype "passive"))
    )
    (net (code "70") (name "Net-(JP12-Pad8)") (class "Default")
      (node (ref "JP12") (pin "8") (pinfunction "8_8") (pintype "passive"))
      (node (ref "LED5") (pin "A") (pinfunction "A_A") (pintype "passive"))
    )
    (net (code "71") (name "Net-(JP12-Pad10)") (class "Default")
      (node (ref "JP12") (pin "10") (pinfunction "10_10") (pintype "passive"))
      (node (ref "LED6") (pin "A") (pinfunction "A_A") (pintype "passive"))
    )
    (net (code "72") (name "Net-(JP12-Pad12)") (class "Default")
      (node (ref "JP12") (pin "12") (pinfunction "12_12") (pintype "passive"))
      (node (ref "LED7") (pin "A") (pinfunction "A_A") (pintype "passive"))
    )
    (net (code "73") (name "Net-(JP12-Pad14)") (class "Default")
      (node (ref "JP12") (pin "14") (pinfunction "14_14") (pintype "passive"))
      (node (ref "LED8") (pin "A") (pinfunction "A_A") (pintype "passive"))
    )
    (net (code "74") (name "Net-(JP12-Pad16)") (class "Default")
      (node (ref "JP12") (pin "16") (pinfunction "16_16") (pintype "passive"))
      (node (ref "LED9") (pin "A") (pinfunction "A_A") (pintype "passive"))
    )
    (net (code "75") (name "Net-(JP14-Pad1)") (class "Default")
      (node (ref "JP14") (pin "1") (pinfunction "1_1") (pintype "passive"))
      (node (ref "R19") (pin "1") (pinfunction "1_1") (pintype "passive"))
      (node (ref "S1") (pin "3") (pinfunction "3_3") (pintype "passive"))
      (node (ref "S1") (pin "4") (pinfunction "4_4") (pintype "passive"))
    )
    (net (code "76") (name "Net-(JP14-Pad2)") (class "Default")
      (node (ref "JP14") (pin "2") (pinfunction "2_2") (pintype "passive"))
      (node (ref "R20") (pin "1") (pinfunction "1_1") (pintype "passive"))
      (node (ref "S2") (pin "3") (pinfunction "3_3") (pintype "passive"))
      (node (ref "S2") (pin "4") (pinfunction "4_4") (pintype "passive"))
    )
    (net (code "77") (name "Net-(JP14-Pad3)") (class "Default")
      (node (ref "JP14") (pin "3") (pinfunction "3_3") (pintype "passive"))
      (node (ref "R21") (pin "1") (pinfunction "1_1") (pintype "passive"))
      (node (ref "S3") (pin "3") (pinfunction "3_3") (pintype "passive"))
      (node (ref "S3") (pin "4") (pinfunction "4_4") (pintype "passive"))
    )
    (net (code "78") (name "Net-(JP14-Pad4)") (class "Default")
      (node (ref "JP14") (pin "4") (pinfunction "4_4") (pintype "passive"))
      (node (ref "R22") (pin "1") (pinfunction "1_1") (pintype "passive"))
      (node (ref "S4") (pin "3") (pinfunction "3_3") (pintype "passive"))
      (node (ref "S4") (pin "4") (pinfunction "4_4") (pintype "passive"))
    )
    (net (code "79") (name "Net-(JP14-Pad5)") (class "Default")
      (node (ref "JP14") (pin "5") (pinfunction "5_5") (pintype "passive"))
      (node (ref "R23") (pin "1") (pinfunction "1_1") (pintype "passive"))
      (node (ref "S5") (pin "3") (pinfunction "3_3") (pintype "passive"))
      (node (ref "S5") (pin "4") (pinfunction "4_4") (pintype "passive"))
    )
    (net (code "80") (name "Net-(LED2-PadC)") (class "Default")
      (node (ref "LED2") (pin "C") (pinfunction "C_C") (pintype "passive"))
      (node (ref "R11") (pin "2") (pinfunction "2_2") (pintype "passive"))
    )
    (net (code "81") (name "Net-(LED3-PadC)") (class "Default")
      (node (ref "LED3") (pin "C") (pinfunction "C_C") (pintype "passive"))
      (node (ref "R12") (pin "2") (pinfunction "2_2") (pintype "passive"))
    )
    (net (code "82") (name "Net-(LED4-PadC)") (class "Default")
      (node (ref "LED4") (pin "C") (pinfunction "C_C") (pintype "passive"))
      (node (ref "R13") (pin "2") (pinfunction "2_2") (pintype "passive"))
    )
    (net (code "83") (name "Net-(LED5-PadC)") (class "Default")
      (node (ref "LED5") (pin "C") (pinfunction "C_C") (pintype "passive"))
      (node (ref "R14") (pin "2") (pinfunction "2_2") (pintype "passive"))
    )
    (net (code "84") (name "Net-(LED6-PadC)") (class "Default")
      (node (ref "LED6") (pin "C") (pinfunction "C_C") (pintype "passive"))
      (node (ref "R15") (pin "2") (pinfunction "2_2") (pintype "passive"))
    )
    (net (code "85") (name "Net-(LED7-PadC)") (class "Default")
      (node (ref "LED7") (pin "C") (pinfunction "C_C") (pintype "passive"))
      (node (ref "R16") (pin "2") (pinfunction "2_2") (pintype "passive"))
    )
    (net (code "86") (name "Net-(LED8-PadC)") (class "Default")
      (node (ref "LED8") (pin "C") (pinfunction "C_C") (pintype "passive"))
      (node (ref "R17") (pin "2") (pinfunction "2_2") (pintype "passive"))
    )
    (net (code "87") (name "Net-(LED9-PadC)") (class "Default")
      (node (ref "LED9") (pin "C") (pinfunction "C_C") (pintype "passive"))
      (node (ref "R18") (pin "2") (pinfunction "2_2") (pintype "passive"))
    )
    (net (code "88") (name "Net-(LED10-PadC)") (class "Default")
      (node (ref "LED10") (pin "C") (pinfunction "C_C") (pintype "passive"))
      (node (ref "R24") (pin "2") (pinfunction "2_2") (pintype "passive"))
    )
    (net (code "89") (name "Net-(U1-SCL)") (class "Default")
      (node (ref "JP2") (pin "2") (pinfunction "2_2") (pintype "passive"))
      (node (ref "R3") (pin "1") (pinfunction "1_1") (pintype "passive"))
      (node (ref "U1") (pin "6") (pinfunction "SCL_6") (pintype "bidirectional"))
    )
    (net (code "90") (name "Net-(U1-SDA)") (class "Default")
      (node (ref "JP2") (pin "3") (pinfunction "3_3") (pintype "passive"))
      (node (ref "R2") (pin "1") (pinfunction "1_1") (pintype "passive"))
      (node (ref "U1") (pin "5") (pinfunction "SDA_5") (pintype "bidirectional"))
    )
    (net (code "91") (name "Net-(U1-SQW{slash}OUT)") (class "Default")
      (node (ref "JP2") (pin "1") (pinfunction "1_1") (pintype "passive"))
      (node (ref "R4") (pin "1") (pinfunction "1_1") (pintype "passive"))
      (node (ref "U1") (pin "7") (pinfunction "SQW/OUT_7") (pintype "bidirectional"))
    )
    (net (code "92") (name "Net-(U1-VBAT)") (class "Default")
      (node (ref "JP7") (pin "2") (pinfunction "2_2") (pintype "passive"))
      (node (ref "U1") (pin "3") (pinfunction "VBAT_3") (pintype "power_in"))
    )
    (net (code "93") (name "Net-(U1-X1)") (class "Default")
      (node (ref "Q1") (pin "2") (pinfunction "2_2") (pintype "passive"))
      (node (ref "U1") (pin "1") (pinfunction "X1_1") (pintype "passive"))
    )
    (net (code "94") (name "Net-(U1-X2)") (class "Default")
      (node (ref "Q1") (pin "1") (pinfunction "1_1") (pintype "passive"))
      (node (ref "U1") (pin "2") (pinfunction "X2_2") (pintype "passive"))
    )
    (net (code "95") (name "Net-(U2-DQ)") (class "Default")
      (node (ref "JP1") (pin "1") (pinfunction "1_1") (pintype "passive"))
      (node (ref "R1") (pin "1") (pinfunction "1_1") (pintype "passive"))
      (node (ref "U2") (pin "2") (pinfunction "DQ_2") (pintype "bidirectional"))
    )
    (net (code "96") (name "unconnected-(IC4A-QE-Pad4)") (class "Default")
      (node (ref "IC4") (pin "4") (pinfunction "QE_4") (pintype "tri_state"))
    )
    (net (code "97") (name "unconnected-(IC4A-QF-Pad5)") (class "Default")
      (node (ref "IC4") (pin "5") (pinfunction "QF_5") (pintype "tri_state"))
    )
    (net (code "98") (name "unconnected-(IC4A-QG-Pad6)") (class "Default")
      (node (ref "IC4") (pin "6") (pinfunction "QG_6") (pintype "tri_state"))
    )
    (net (code "99") (name "unconnected-(IC4A-QH*-Pad9)") (class "Default")
      (node (ref "IC4") (pin "9") (pinfunction "QH*_9") (pintype "tri_state"))
    )
    (net (code "100") (name "unconnected-(IC4A-QH-Pad7)") (class "Default")
      (node (ref "IC4") (pin "7") (pinfunction "QH_7") (pintype "tri_state"))
    )
    (net (code "101") (name "unconnected-(JP15-Pad1)") (class "Default")
      (node (ref "JP15") (pin "1") (pinfunction "1_1") (pintype "passive"))
    )
    (net (code "102") (name "unconnected-(JP16-Pad1)") (class "Default")
      (node (ref "JP16") (pin "1") (pinfunction "1_1") (pintype "passive"))
    )
  )
)
